# RTL_-_ETH_PHY.net
KiCad netlist of a schematic drawn in Altium Designer
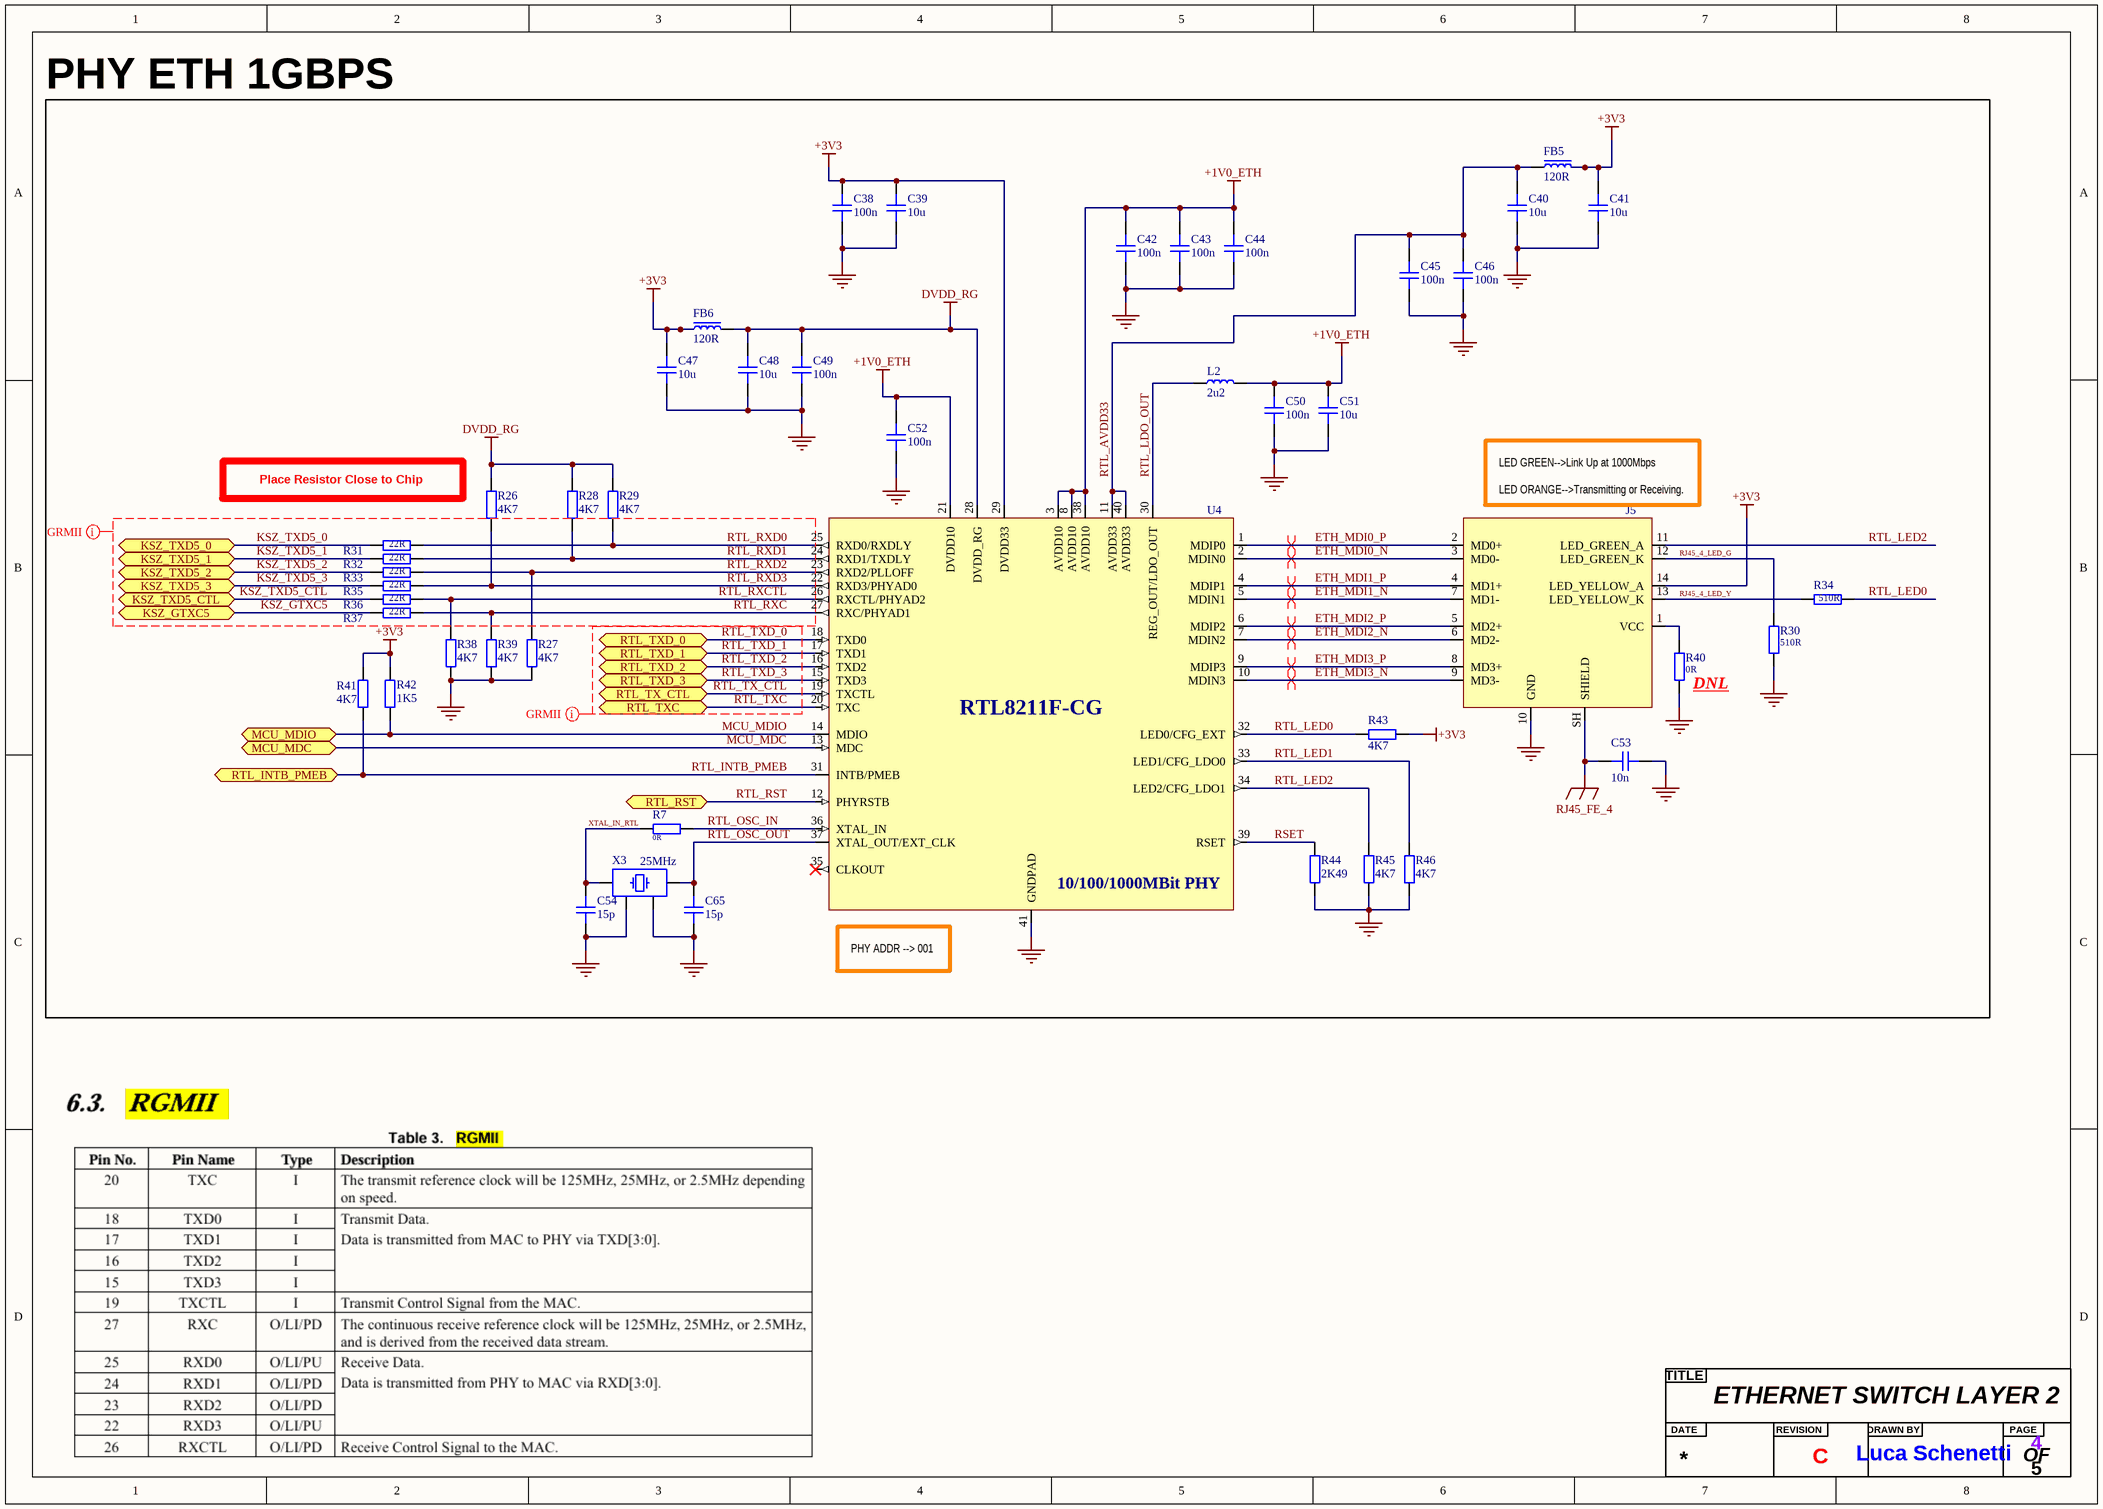
[diagram p0: RTL - ETH PHY.SchDoc]

(export (version "E")
  (design (tool "Eeschema 10.0.6"))
  (components
    (comp (ref "C38")
      (value "100n")
      (footprint "CAP_0603")
      (description "Capacitor SMD 0603 [C14663]")
      (libsource (lib "Schematic-Lib-PhilsLab") (part "CAP_0603"))
    )
    (comp (ref "C39")
      (value "10u")
      (footprint "CAP_0603")
      (description "Capacitor SMD 0603 [C96446]")
      (libsource (lib "Schematic-Lib-PhilsLab") (part "CAP_0603"))
    )
    (comp (ref "C40")
      (value "10u")
      (footprint "CAP_0603")
      (description "Capacitor SMD 0603 [C96446]")
      (libsource (lib "Schematic-Lib-PhilsLab") (part "CAP_0603"))
    )
    (comp (ref "C41")
      (value "10u")
      (footprint "CAP_0603")
      (description "Capacitor SMD 0603 [C96446]")
      (libsource (lib "Schematic-Lib-PhilsLab") (part "CAP_0603"))
    )
    (comp (ref "C42")
      (value "100n")
      (footprint "CAP_0603")
      (description "Capacitor SMD 0603 [C14663]")
      (libsource (lib "Schematic-Lib-PhilsLab") (part "CAP_0603"))
    )
    (comp (ref "C43")
      (value "100n")
      (footprint "CAP_0603")
      (description "Capacitor SMD 0603 [C14663]")
      (libsource (lib "Schematic-Lib-PhilsLab") (part "CAP_0603"))
    )
    (comp (ref "C44")
      (value "100n")
      (footprint "CAP_0603")
      (description "Capacitor SMD 0603 [C14663]")
      (libsource (lib "Schematic-Lib-PhilsLab") (part "CAP_0603"))
    )
    (comp (ref "C45")
      (value "100n")
      (footprint "CAP_0603")
      (description "Capacitor SMD 0603 [C14663]")
      (libsource (lib "Schematic-Lib-PhilsLab") (part "CAP_0603"))
    )
    (comp (ref "C46")
      (value "100n")
      (footprint "CAP_0603")
      (description "Capacitor SMD 0603 [C14663]")
      (libsource (lib "Schematic-Lib-PhilsLab") (part "CAP_0603"))
    )
    (comp (ref "C47")
      (value "10u")
      (footprint "CAP_0603")
      (description "Capacitor SMD 0603 [C96446]")
      (libsource (lib "Schematic-Lib-PhilsLab") (part "CAP_0603"))
    )
    (comp (ref "C48")
      (value "10u")
      (footprint "CAP_0603")
      (description "Capacitor SMD 0603 [C96446]")
      (libsource (lib "Schematic-Lib-PhilsLab") (part "CAP_0603"))
    )
    (comp (ref "C49")
      (value "100n")
      (footprint "CAP_0603")
      (description "Capacitor SMD 0603 [C14663]")
      (libsource (lib "Schematic-Lib-PhilsLab") (part "CAP_0603"))
    )
    (comp (ref "C50")
      (value "100n")
      (footprint "CAP_0603")
      (description "Capacitor SMD 0603 [C14663]")
      (libsource (lib "Schematic-Lib-PhilsLab") (part "CAP_0603"))
    )
    (comp (ref "C51")
      (value "10u")
      (footprint "CAP_0603")
      (description "Capacitor SMD 0603 [C96446]")
      (libsource (lib "Schematic-Lib-PhilsLab") (part "CAP_0603"))
    )
    (comp (ref "C52")
      (value "100n")
      (footprint "CAP_0603")
      (description "Capacitor SMD 0603 [C14663]")
      (libsource (lib "Schematic-Lib-PhilsLab") (part "CAP_0603"))
    )
    (comp (ref "C53")
      (value "10n")
      (footprint "CAP_1206")
      (description "[C1846]")
      (libsource (lib "Schematic-Lib-PhilsLab") (part "CAP_1206"))
    )
    (comp (ref "C54")
      (value "15p")
      (footprint "CAP_0402")
      (description "Capacitor SMD 0402 [C1548]")
      (libsource (lib "Schematic-Lib-PhilsLab") (part "CAP_0402"))
    )
    (comp (ref "C65")
      (value "15p")
      (footprint "CAP_0402")
      (description "Capacitor SMD 0402 [C1548]")
      (libsource (lib "Schematic-Lib-PhilsLab") (part "CAP_0402"))
    )
    (comp (ref "FB5")
      (value "120R")
      (footprint "FB_0603")
      (description "Ferrite Bead SMD 0603[C76892]")
      (libsource (lib "Schematic-Lib-PhilsLab") (part "FB_0603"))
    )
    (comp (ref "FB6")
      (value "120R")
      (footprint "FB_0603")
      (description "Ferrite Bead SMD 0603[C76892]")
      (libsource (lib "") (part "FB_0603_1"))
    )
    (comp (ref "J5")
      (value "100/1000Base-T RJ45 MAGJACK")
      (footprint "HR911130A")
      (description "[C54408]")
      (fields (field (name "MANUFACTURER") "Hanrun") (field (name "MANUFACTURER PART NUMBER") "HR911130A"))
      (libsource (lib "My_Library") (part "HR911130A"))
    )
    (comp (ref "L2")
      (value "2u2")
      (footprint "IND_1008")
      (description "[C3002540]")
      (libsource (lib "Schematic-Lib-PhilsLab") (part "IND_1008"))
    )
    (comp (ref "R7")
      (value "0R")
      (footprint "RES_0402")
      (description "Resistor SMD 0402 [C17168]")
      (libsource (lib "Schematic-Lib-PhilsLab") (part "RES_0402"))
    )
    (comp (ref "R26")
      (value "4K7")
      (footprint "RES_0402")
      (description "[C25900]")
      (libsource (lib "Schematic-Lib-PhilsLab") (part "RES_0402"))
    )
    (comp (ref "R27")
      (value "4K7")
      (footprint "RES_0402")
      (description "[C25900]")
      (libsource (lib "Schematic-Lib-PhilsLab") (part "RES_0402"))
    )
    (comp (ref "R28")
      (value "4K7")
      (footprint "RES_0402")
      (description "[C25900]")
      (libsource (lib "Schematic-Lib-PhilsLab") (part "RES_0402"))
    )
    (comp (ref "R29")
      (value "4K7")
      (footprint "RES_0402")
      (description "[C25900]")
      (libsource (lib "Schematic-Lib-PhilsLab") (part "RES_0402"))
    )
    (comp (ref "R30")
      (value "510R")
      (footprint "RES_0603")
      (description "[C23193]")
      (libsource (lib "Schematic-Lib-PhilsLab") (part "RES_0603"))
    )
    (comp (ref "R31")
      (value "22R")
      (footprint "RES_0402")
      (description "Resistor SMD 0402 [C25092]")
      (libsource (lib "Schematic-Lib-PhilsLab") (part "RES_0402"))
    )
    (comp (ref "R32")
      (value "22R")
      (footprint "RES_0402")
      (description "Resistor SMD 0402 [C25092]")
      (libsource (lib "Schematic-Lib-PhilsLab") (part "RES_0402"))
    )
    (comp (ref "R33")
      (value "22R")
      (footprint "RES_0402")
      (description "Resistor SMD 0402 [C25092]")
      (libsource (lib "Schematic-Lib-PhilsLab") (part "RES_0402"))
    )
    (comp (ref "R34")
      (value "510R")
      (footprint "RES_0603")
      (description "[C23193]")
      (libsource (lib "Schematic-Lib-PhilsLab") (part "RES_0603"))
    )
    (comp (ref "R35")
      (value "22R")
      (footprint "RES_0402")
      (description "Resistor SMD 0402 [C25092]")
      (libsource (lib "Schematic-Lib-PhilsLab") (part "RES_0402"))
    )
    (comp (ref "R36")
      (value "22R")
      (footprint "RES_0402")
      (description "Resistor SMD 0402 [C25092]")
      (libsource (lib "Schematic-Lib-PhilsLab") (part "RES_0402"))
    )
    (comp (ref "R37")
      (value "22R")
      (footprint "RES_0402")
      (description "Resistor SMD 0402 [C25092]")
      (libsource (lib "Schematic-Lib-PhilsLab") (part "RES_0402"))
    )
    (comp (ref "R38")
      (value "4K7")
      (footprint "RES_0402")
      (description "[C25900]")
      (libsource (lib "Schematic-Lib-PhilsLab") (part "RES_0402"))
    )
    (comp (ref "R39")
      (value "4K7")
      (footprint "RES_0402")
      (description "[C25900]")
      (libsource (lib "Schematic-Lib-PhilsLab") (part "RES_0402"))
    )
    (comp (ref "R40")
      (value "0R")
      (footprint "RES_0402")
      (description "Resistor SMD 0402")
      (libsource (lib "Schematic-Lib-PhilsLab") (part "RES_0402"))
    )
    (comp (ref "R41")
      (value "4K7")
      (footprint "RES_0603")
      (description "[C23162]")
      (libsource (lib "Schematic-Lib-PhilsLab") (part "RES_0603"))
    )
    (comp (ref "R42")
      (value "1K5")
      (footprint "RES_0603")
      (description "[C22843]")
      (libsource (lib "Schematic-Lib-PhilsLab") (part "RES_0603"))
    )
    (comp (ref "R43")
      (value "4K7")
      (footprint "RES_0603")
      (description "[C23162]")
      (libsource (lib "Schematic-Lib-PhilsLab") (part "RES_0603"))
    )
    (comp (ref "R44")
      (value "2K49")
      (footprint "RES_0603")
      (description "[C22908]")
      (libsource (lib "Schematic-Lib-PhilsLab") (part "RES_0603"))
    )
    (comp (ref "R45")
      (value "4K7")
      (footprint "RES_0603")
      (description "[C23162]")
      (libsource (lib "Schematic-Lib-PhilsLab") (part "RES_0603"))
    )
    (comp (ref "R46")
      (value "4K7")
      (footprint "RES_0603")
      (description "[C23162]")
      (libsource (lib "Schematic-Lib-PhilsLab") (part "RES_0603"))
    )
    (comp (ref "U4")
      (value "PHY ETH 10/100/1000M")
      (footprint "RTL8211F-CG")
      (description "[C187932]")
      (fields (field (name "MANUFACTURER") "Realtek") (field (name "MANUFACTURER PART NUMBER") "RTL8211F-CG"))
      (libsource (lib "My_Library") (part "RTL8211F-CG"))
    )
    (comp (ref "X3")
      (value "25MHz")
      (footprint "XTAL_3225")
      (description "Crystal SMD 24MHz 10PPM 7pF 3225 [C9006]")
      (fields
        (field (name "MANUFACTURER") "Epson")
        (field (name "MANUFACTURER PART NUMBER") "TSX-3225 24.0000MF15X-AC")
      )
      (libsource (lib "Schematic-Lib-PhilsLab") (part "TSX-3225_24.0000MF15X-AC"))
    )
  )
  (nets
    (net (code "1") (name "+1V0_ETH") (class "Default")
      (node (ref "C42") (pin "2") (pinfunction "2_2") (pintype "passive"))
      (node (ref "C43") (pin "2") (pinfunction "2_2") (pintype "passive"))
      (node (ref "C44") (pin "2") (pinfunction "2_2") (pintype "passive"))
      (node (ref "C50") (pin "2") (pinfunction "2_2") (pintype "passive"))
      (node (ref "C51") (pin "2") (pinfunction "2_2") (pintype "passive"))
      (node (ref "C52") (pin "2") (pinfunction "2_2") (pintype "passive"))
      (node (ref "L2") (pin "2") (pinfunction "2_2") (pintype "passive"))
      (node (ref "U4") (pin "21") (pinfunction "DVDD10_21") (pintype "power_in"))
      (node (ref "U4") (pin "3") (pinfunction "AVDD10_3") (pintype "power_in"))
      (node (ref "U4") (pin "38") (pinfunction "AVDD10_38") (pintype "power_in"))
      (node (ref "U4") (pin "8") (pinfunction "AVDD10_8") (pintype "power_in"))
    )
    (net (code "2") (name "+3V3") (class "Default")
      (node (ref "C38") (pin "2") (pinfunction "2_2") (pintype "passive"))
      (node (ref "C39") (pin "2") (pinfunction "2_2") (pintype "passive"))
      (node (ref "C41") (pin "2") (pinfunction "2_2") (pintype "passive"))
      (node (ref "C47") (pin "2") (pinfunction "2_2") (pintype "passive"))
      (node (ref "FB5") (pin "2") (pinfunction "2_2") (pintype "passive"))
      (node (ref "FB6") (pin "2") (pinfunction "2_2") (pintype "passive"))
      (node (ref "J5") (pin "14") (pinfunction "LED_YELLOW_A_14") (pintype "passive"))
      (node (ref "R41") (pin "2") (pinfunction "2_2") (pintype "passive"))
      (node (ref "R42") (pin "2") (pinfunction "2_2") (pintype "passive"))
      (node (ref "R43") (pin "1") (pinfunction "1_1") (pintype "passive"))
      (node (ref "U4") (pin "29") (pinfunction "DVDD33_29") (pintype "power_in"))
    )
    (net (code "3") (name "/ETH_MDI0_N") (class "Default")
      (node (ref "J5") (pin "3") (pinfunction "MD0-_3") (pintype "passive"))
      (node (ref "U4") (pin "2") (pinfunction "MDIN0_2") (pintype "bidirectional"))
    )
    (net (code "4") (name "/ETH_MDI0_P") (class "Default")
      (node (ref "J5") (pin "2") (pinfunction "MD0+_2") (pintype "passive"))
      (node (ref "U4") (pin "1") (pinfunction "MDIP0_1") (pintype "bidirectional"))
    )
    (net (code "5") (name "/ETH_MDI1_N") (class "Default")
      (node (ref "J5") (pin "7") (pinfunction "MD1-_7") (pintype "passive"))
      (node (ref "U4") (pin "5") (pinfunction "MDIN1_5") (pintype "bidirectional"))
    )
    (net (code "6") (name "/ETH_MDI1_P") (class "Default")
      (node (ref "J5") (pin "4") (pinfunction "MD1+_4") (pintype "passive"))
      (node (ref "U4") (pin "4") (pinfunction "MDIP1_4") (pintype "bidirectional"))
    )
    (net (code "7") (name "/ETH_MDI2_N") (class "Default")
      (node (ref "J5") (pin "6") (pinfunction "MD2-_6") (pintype "passive"))
      (node (ref "U4") (pin "7") (pinfunction "MDIN2_7") (pintype "bidirectional"))
    )
    (net (code "8") (name "/ETH_MDI2_P") (class "Default")
      (node (ref "J5") (pin "5") (pinfunction "MD2+_5") (pintype "passive"))
      (node (ref "U4") (pin "6") (pinfunction "MDIP2_6") (pintype "bidirectional"))
    )
    (net (code "9") (name "/ETH_MDI3_N") (class "Default")
      (node (ref "J5") (pin "9") (pinfunction "MD3-_9") (pintype "passive"))
      (node (ref "U4") (pin "10") (pinfunction "MDIN3_10") (pintype "bidirectional"))
    )
    (net (code "10") (name "/ETH_MDI3_P") (class "Default")
      (node (ref "J5") (pin "8") (pinfunction "MD3+_8") (pintype "passive"))
      (node (ref "U4") (pin "9") (pinfunction "MDIP3_9") (pintype "bidirectional"))
    )
    (net (code "11") (name "/KSZ_GTXC5") (class "Default")
      (node (ref "R37") (pin "1") (pinfunction "1_1") (pintype "passive"))
    )
    (net (code "12") (name "/KSZ_TXD5_0") (class "Default")
      (node (ref "R31") (pin "1") (pinfunction "1_1") (pintype "passive"))
    )
    (net (code "13") (name "/KSZ_TXD5_1") (class "Default")
      (node (ref "R32") (pin "1") (pinfunction "1_1") (pintype "passive"))
    )
    (net (code "14") (name "/KSZ_TXD5_2") (class "Default")
      (node (ref "R33") (pin "1") (pinfunction "1_1") (pintype "passive"))
    )
    (net (code "15") (name "/KSZ_TXD5_3") (class "Default")
      (node (ref "R35") (pin "1") (pinfunction "1_1") (pintype "passive"))
    )
    (net (code "16") (name "/KSZ_TXD5_CTL") (class "Default")
      (node (ref "R36") (pin "1") (pinfunction "1_1") (pintype "passive"))
    )
    (net (code "17") (name "/MCU_MDC") (class "Default")
      (node (ref "U4") (pin "13") (pinfunction "MDC_13") (pintype "input"))
    )
    (net (code "18") (name "/MCU_MDIO") (class "Default")
      (node (ref "R42") (pin "1") (pinfunction "1_1") (pintype "passive"))
      (node (ref "U4") (pin "14") (pinfunction "MDIO_14") (pintype "bidirectional"))
    )
    (net (code "19") (name "/RJ45_4_LED_G") (class "Default")
      (node (ref "J5") (pin "12") (pinfunction "LED_GREEN_K_12") (pintype "passive"))
      (node (ref "R30") (pin "1") (pinfunction "1_1") (pintype "passive"))
    )
    (net (code "20") (name "/RJ45_4_LED_Y") (class "Default")
      (node (ref "J5") (pin "13") (pinfunction "LED_YELLOW_K_13") (pintype "passive"))
      (node (ref "R34") (pin "2") (pinfunction "2_2") (pintype "passive"))
    )
    (net (code "21") (name "/RSET") (class "Default")
      (node (ref "R44") (pin "1") (pinfunction "1_1") (pintype "passive"))
      (node (ref "U4") (pin "39") (pinfunction "RSET_39") (pintype "output"))
    )
    (net (code "22") (name "/RTL_AVDD33") (class "Default")
      (node (ref "C40") (pin "2") (pinfunction "2_2") (pintype "passive"))
      (node (ref "C45") (pin "2") (pinfunction "2_2") (pintype "passive"))
      (node (ref "C46") (pin "2") (pinfunction "2_2") (pintype "passive"))
      (node (ref "FB5") (pin "1") (pinfunction "1_1") (pintype "passive"))
      (node (ref "U4") (pin "11") (pinfunction "AVDD33_11") (pintype "power_in"))
      (node (ref "U4") (pin "40") (pinfunction "AVDD33_40") (pintype "power_in"))
    )
    (net (code "23") (name "/RTL_INTB_PMEB") (class "Default")
      (node (ref "R41") (pin "1") (pinfunction "1_1") (pintype "passive"))
      (node (ref "U4") (pin "31") (pinfunction "INTB/PMEB_31") (pintype "passive"))
    )
    (net (code "24") (name "/RTL_LDO_OUT") (class "Default")
      (node (ref "L2") (pin "1") (pinfunction "1_1") (pintype "passive"))
      (node (ref "U4") (pin "30") (pinfunction "REG_OUT/LDO_OUT_30") (pintype "power_in"))
    )
    (net (code "25") (name "/RTL_LED0") (class "Default")
      (node (ref "R34") (pin "1") (pinfunction "1_1") (pintype "passive"))
      (node (ref "R43") (pin "2") (pinfunction "2_2") (pintype "passive"))
      (node (ref "U4") (pin "32") (pinfunction "LED0/CFG_EXT_32") (pintype "output"))
    )
    (net (code "26") (name "/RTL_LED1") (class "Default")
      (node (ref "R46") (pin "1") (pinfunction "1_1") (pintype "passive"))
      (node (ref "U4") (pin "33") (pinfunction "LED1/CFG_LDO0_33") (pintype "output"))
    )
    (net (code "27") (name "/RTL_LED2") (class "Default")
      (node (ref "J5") (pin "11") (pinfunction "LED_GREEN_A_11") (pintype "passive"))
      (node (ref "R45") (pin "1") (pinfunction "1_1") (pintype "passive"))
      (node (ref "U4") (pin "34") (pinfunction "LED2/CFG_LDO1_34") (pintype "output"))
    )
    (net (code "28") (name "/RTL_OSC_IN") (class "Default")
      (node (ref "R7") (pin "2") (pinfunction "2_2") (pintype "passive"))
      (node (ref "U4") (pin "36") (pinfunction "XTAL_IN_36") (pintype "input"))
    )
    (net (code "29") (name "/RTL_OSC_OUT") (class "Default")
      (node (ref "C65") (pin "2") (pinfunction "2_2") (pintype "passive"))
      (node (ref "U4") (pin "37") (pinfunction "XTAL_OUT/EXT_CLK_37") (pintype "passive"))
      (node (ref "X3") (pin "1") (pinfunction "1_1") (pintype "passive"))
    )
    (net (code "30") (name "/RTL_RST") (class "Default")
      (node (ref "U4") (pin "12") (pinfunction "PHYRSTB_12") (pintype "input"))
    )
    (net (code "31") (name "/RTL_RXC") (class "Default")
      (node (ref "R37") (pin "2") (pinfunction "2_2") (pintype "passive"))
      (node (ref "R39") (pin "2") (pinfunction "2_2") (pintype "passive"))
      (node (ref "U4") (pin "27") (pinfunction "RXC/PHYAD1_27") (pintype "output"))
    )
    (net (code "32") (name "/RTL_RXCTL") (class "Default")
      (node (ref "R36") (pin "2") (pinfunction "2_2") (pintype "passive"))
      (node (ref "R38") (pin "2") (pinfunction "2_2") (pintype "passive"))
      (node (ref "U4") (pin "26") (pinfunction "RXCTL/PHYAD2_26") (pintype "output"))
    )
    (net (code "33") (name "/RTL_RXD0") (class "Default")
      (node (ref "R29") (pin "1") (pinfunction "1_1") (pintype "passive"))
      (node (ref "R31") (pin "2") (pinfunction "2_2") (pintype "passive"))
      (node (ref "U4") (pin "25") (pinfunction "RXD0/RXDLY_25") (pintype "output"))
    )
    (net (code "34") (name "/RTL_RXD1") (class "Default")
      (node (ref "R28") (pin "1") (pinfunction "1_1") (pintype "passive"))
      (node (ref "R32") (pin "2") (pinfunction "2_2") (pintype "passive"))
      (node (ref "U4") (pin "24") (pinfunction "RXD1/TXDLY_24") (pintype "output"))
    )
    (net (code "35") (name "/RTL_RXD2") (class "Default")
      (node (ref "R27") (pin "2") (pinfunction "2_2") (pintype "passive"))
      (node (ref "R33") (pin "2") (pinfunction "2_2") (pintype "passive"))
      (node (ref "U4") (pin "23") (pinfunction "RXD2/PLLOFF_23") (pintype "output"))
    )
    (net (code "36") (name "/RTL_RXD3") (class "Default")
      (node (ref "R26") (pin "1") (pinfunction "1_1") (pintype "passive"))
      (node (ref "R35") (pin "2") (pinfunction "2_2") (pintype "passive"))
      (node (ref "U4") (pin "22") (pinfunction "RXD3/PHYAD0_22") (pintype "output"))
    )
    (net (code "37") (name "/RTL_TXC") (class "Default")
      (node (ref "U4") (pin "20") (pinfunction "TXC_20") (pintype "input"))
    )
    (net (code "38") (name "/RTL_TXD_0") (class "Default")
      (node (ref "U4") (pin "18") (pinfunction "TXD0_18") (pintype "input"))
    )
    (net (code "39") (name "/RTL_TXD_1") (class "Default")
      (node (ref "U4") (pin "17") (pinfunction "TXD1_17") (pintype "input"))
    )
    (net (code "40") (name "/RTL_TXD_2") (class "Default")
      (node (ref "U4") (pin "16") (pinfunction "TXD2_16") (pintype "input"))
    )
    (net (code "41") (name "/RTL_TXD_3") (class "Default")
      (node (ref "U4") (pin "15") (pinfunction "TXD3_15") (pintype "input"))
    )
    (net (code "42") (name "/RTL_TX_CTL") (class "Default")
      (node (ref "U4") (pin "19") (pinfunction "TXCTL_19") (pintype "input"))
    )
    (net (code "43") (name "/XTAL_IN_RTL") (class "Default")
      (node (ref "C54") (pin "2") (pinfunction "2_2") (pintype "passive"))
      (node (ref "R7") (pin "1") (pinfunction "1_1") (pintype "passive"))
      (node (ref "X3") (pin "3") (pinfunction "3_3") (pintype "passive"))
    )
    (net (code "44") (name "DVDD_RG") (class "Default")
      (node (ref "C48") (pin "2") (pinfunction "2_2") (pintype "passive"))
      (node (ref "C49") (pin "2") (pinfunction "2_2") (pintype "passive"))
      (node (ref "FB6") (pin "1") (pinfunction "1_1") (pintype "passive"))
      (node (ref "R26") (pin "2") (pinfunction "2_2") (pintype "passive"))
      (node (ref "R28") (pin "2") (pinfunction "2_2") (pintype "passive"))
      (node (ref "R29") (pin "2") (pinfunction "2_2") (pintype "passive"))
      (node (ref "U4") (pin "28") (pinfunction "DVDD_RG_28") (pintype "power_in"))
    )
    (net (code "45") (name "GND") (class "Default")
      (node (ref "C38") (pin "1") (pinfunction "1_1") (pintype "passive"))
      (node (ref "C39") (pin "1") (pinfunction "1_1") (pintype "passive"))
      (node (ref "C40") (pin "1") (pinfunction "1_1") (pintype "passive"))
      (node (ref "C41") (pin "1") (pinfunction "1_1") (pintype "passive"))
      (node (ref "C42") (pin "1") (pinfunction "1_1") (pintype "passive"))
      (node (ref "C43") (pin "1") (pinfunction "1_1") (pintype "passive"))
      (node (ref "C44") (pin "1") (pinfunction "1_1") (pintype "passive"))
      (node (ref "C45") (pin "1") (pinfunction "1_1") (pintype "passive"))
      (node (ref "C46") (pin "1") (pinfunction "1_1") (pintype "passive"))
      (node (ref "C47") (pin "1") (pinfunction "1_1") (pintype "passive"))
      (node (ref "C48") (pin "1") (pinfunction "1_1") (pintype "passive"))
      (node (ref "C49") (pin "1") (pinfunction "1_1") (pintype "passive"))
      (node (ref "C50") (pin "1") (pinfunction "1_1") (pintype "passive"))
      (node (ref "C51") (pin "1") (pinfunction "1_1") (pintype "passive"))
      (node (ref "C52") (pin "1") (pinfunction "1_1") (pintype "passive"))
      (node (ref "C53") (pin "2") (pinfunction "2_2") (pintype "passive"))
      (node (ref "C54") (pin "1") (pinfunction "1_1") (pintype "passive"))
      (node (ref "C65") (pin "1") (pinfunction "1_1") (pintype "passive"))
      (node (ref "J5") (pin "10") (pinfunction "GND_10") (pintype "passive"))
      (node (ref "R27") (pin "1") (pinfunction "1_1") (pintype "passive"))
      (node (ref "R30") (pin "2") (pinfunction "2_2") (pintype "passive"))
      (node (ref "R38") (pin "1") (pinfunction "1_1") (pintype "passive"))
      (node (ref "R39") (pin "1") (pinfunction "1_1") (pintype "passive"))
      (node (ref "R40") (pin "1") (pinfunction "1_1") (pintype "passive"))
      (node (ref "R44") (pin "2") (pinfunction "2_2") (pintype "passive"))
      (node (ref "R45") (pin "2") (pinfunction "2_2") (pintype "passive"))
      (node (ref "R46") (pin "2") (pinfunction "2_2") (pintype "passive"))
      (node (ref "U4") (pin "41") (pinfunction "GNDPAD_41") (pintype "power_in"))
      (node (ref "X3") (pin "2") (pinfunction "2_2") (pintype "passive"))
      (node (ref "X3") (pin "4") (pinfunction "4_4") (pintype "passive"))
    )
    (net (code "46") (name "Net-(J5-VCC)") (class "Default")
      (node (ref "J5") (pin "1") (pinfunction "VCC_1") (pintype "passive"))
      (node (ref "R40") (pin "2") (pinfunction "2_2") (pintype "passive"))
    )
    (net (code "47") (name "RJ45_FE_4") (class "Default")
      (node (ref "C53") (pin "1") (pinfunction "1_1") (pintype "passive"))
      (node (ref "J5") (pin "SH") (pinfunction "SHIELD_SH") (pintype "passive"))
    )
    (net (code "48") (name "unconnected-(U4-CLKOUT-Pad35)") (class "Default")
      (node (ref "U4") (pin "35") (pinfunction "CLKOUT_35") (pintype "output+no_connect"))
    )
  )
)
